# reed-door-sensor.net
KiCad netlist of a schematic drawn in EAGLE
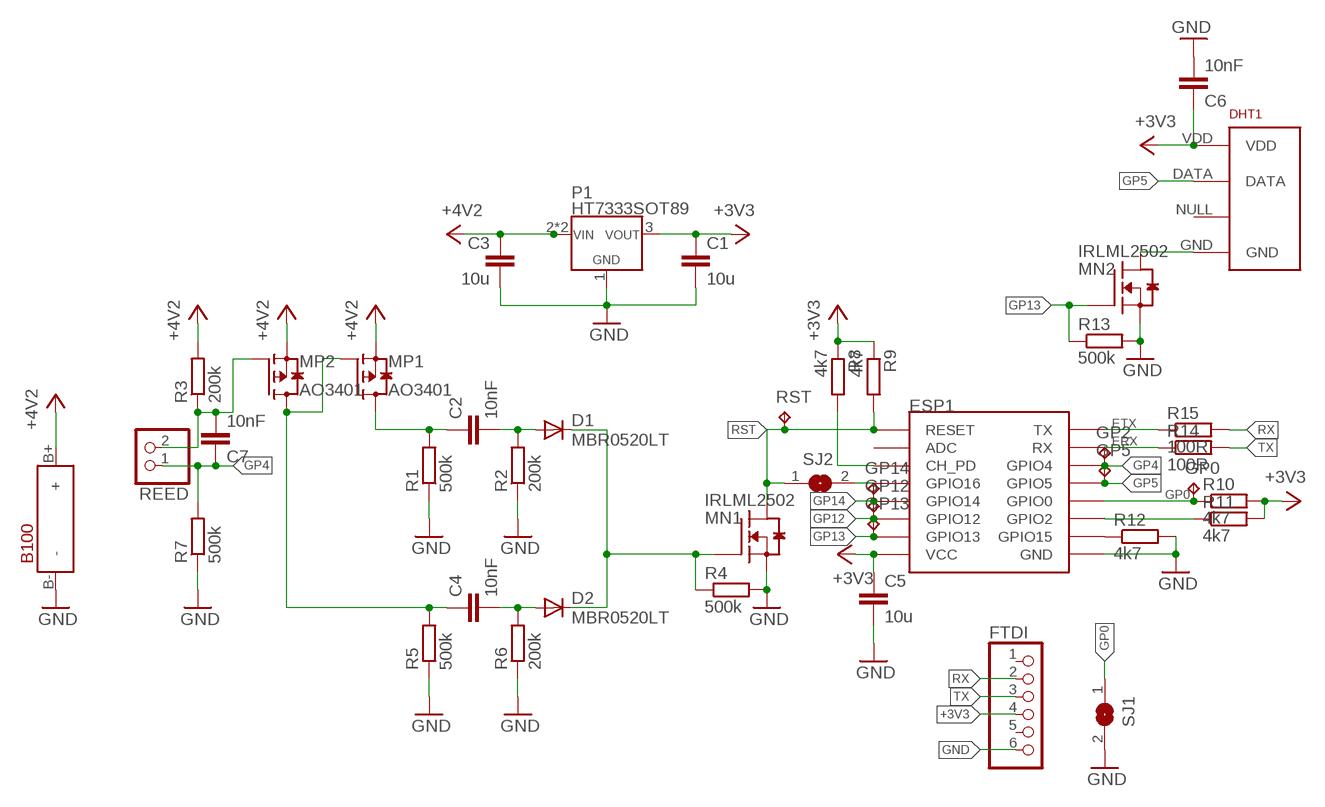
[diagram p0: schematic, sheet 1]

(export (version "E")
  (design (tool "Eeschema 10.0.6"))
  (components
    (comp (ref "B100")
      (value "18650_1X")
      (footprint "eagle-import:18650_HOLDER_1X")
      (libsource (lib "eagle-import") (part "18650_1X"))
    )
    (comp (ref "C1")
      (value "10u")
      (footprint "eagle-import:C1206")
      (libsource (lib "eagle-import") (part "C-EUC1206"))
    )
    (comp (ref "C2")
      (value "10nF")
      (footprint "eagle-import:C0805")
      (libsource (lib "eagle-import") (part "C-EUC0805"))
    )
    (comp (ref "C3")
      (value "10u")
      (footprint "eagle-import:C1206")
      (libsource (lib "eagle-import") (part "C-EUC1206"))
    )
    (comp (ref "C4")
      (value "10nF")
      (footprint "eagle-import:C0805")
      (libsource (lib "eagle-import") (part "C-EUC0805"))
    )
    (comp (ref "C5")
      (value "10u")
      (footprint "eagle-import:C1206")
      (libsource (lib "eagle-import") (part "C-EUC1206"))
    )
    (comp (ref "C6")
      (value "10nF")
      (footprint "eagle-import:C0805")
      (libsource (lib "eagle-import") (part "C-EUC0805"))
    )
    (comp (ref "C7")
      (value "10nF")
      (footprint "eagle-import:C0805")
      (libsource (lib "eagle-import") (part "C-EUC0805"))
    )
    (comp (ref "D1")
      (value "MBR0520LT")
      (footprint "eagle-import:SOD123")
      (libsource (lib "eagle-import") (part "MBR0520LT"))
    )
    (comp (ref "D2")
      (value "MBR0520LT")
      (footprint "eagle-import:SOD123")
      (libsource (lib "eagle-import") (part "MBR0520LT"))
    )
    (comp (ref "DHT1")
      (value "RHT03_DHT-22_AM2302")
      (footprint "eagle-import:RHT03_DHT-22")
      (libsource (lib "eagle-import") (part "RHT03_DHT-22_AM2302"))
    )
    (comp (ref "ESP1")
      (value "ESP12SMD")
      (footprint "eagle-import:ESP12-SMD")
      (libsource (lib "eagle-import") (part "ESP12SMD"))
    )
    (comp (ref "FTDI")
      (value "PINHD-1X06_2.54-S")
      (footprint "eagle-import:1X06-S")
      (libsource (lib "eagle-import") (part "PINHD-1X06_2.54-S"))
    )
    (comp (ref "GP0")
      (value "TPB2,54")
      (footprint "eagle-import:B2,54")
      (libsource (lib "eagle-import") (part "TPB2,54"))
    )
    (comp (ref "GP2")
      (value "TPB1,27")
      (footprint "eagle-import:B1,27")
      (libsource (lib "eagle-import") (part "TPB1,27"))
    )
    (comp (ref "GP5")
      (value "TPB1,27")
      (footprint "eagle-import:B1,27")
      (libsource (lib "eagle-import") (part "TPB1,27"))
    )
    (comp (ref "GP12")
      (value "TPB1,27")
      (footprint "eagle-import:B1,27")
      (libsource (lib "eagle-import") (part "TPB1,27"))
    )
    (comp (ref "GP13")
      (value "TPB1,27")
      (footprint "eagle-import:B1,27")
      (libsource (lib "eagle-import") (part "TPB1,27"))
    )
    (comp (ref "GP14")
      (value "TPB1,27")
      (footprint "eagle-import:B1,27")
      (libsource (lib "eagle-import") (part "TPB1,27"))
    )
    (comp (ref "MN1")
      (value "IRLML2502")
      (footprint "eagle-import:SOT23")
      (libsource (lib "eagle-import") (part "N-CH_IRLML2502"))
    )
    (comp (ref "MN2")
      (value "IRLML2502")
      (footprint "eagle-import:SOT23")
      (libsource (lib "eagle-import") (part "N-CH_IRLML2502"))
    )
    (comp (ref "MP1")
      (value "AO3401")
      (footprint "eagle-import:SOT23")
      (libsource (lib "eagle-import") (part "P-CH_AO3401"))
    )
    (comp (ref "MP2")
      (value "AO3401")
      (footprint "eagle-import:SOT23")
      (libsource (lib "eagle-import") (part "P-CH_AO3401"))
    )
    (comp (ref "P1")
      (value "HT7333SOT89")
      (footprint "eagle-import:SOT89")
      (libsource (lib "eagle-import") (part "HT7333SOT89"))
    )
    (comp (ref "R1")
      (value "500k")
      (footprint "eagle-import:M0805")
      (libsource (lib "eagle-import") (part "R-EU_M0805"))
    )
    (comp (ref "R2")
      (value "200k")
      (footprint "eagle-import:M0805")
      (libsource (lib "eagle-import") (part "R-EU_M0805"))
    )
    (comp (ref "R3")
      (value "200k")
      (footprint "eagle-import:M0805")
      (libsource (lib "eagle-import") (part "R-EU_M0805"))
    )
    (comp (ref "R4")
      (value "500k")
      (footprint "eagle-import:M0805")
      (libsource (lib "eagle-import") (part "R-EU_M0805"))
    )
    (comp (ref "R5")
      (value "500k")
      (footprint "eagle-import:M0805")
      (libsource (lib "eagle-import") (part "R-EU_M0805"))
    )
    (comp (ref "R6")
      (value "200k")
      (footprint "eagle-import:M0805")
      (libsource (lib "eagle-import") (part "R-EU_M0805"))
    )
    (comp (ref "R7")
      (value "500k")
      (footprint "eagle-import:M0805")
      (libsource (lib "eagle-import") (part "R-EU_M0805"))
    )
    (comp (ref "R8")
      (value "4k7")
      (footprint "eagle-import:M0805")
      (libsource (lib "eagle-import") (part "R-EU_M0805"))
    )
    (comp (ref "R9")
      (value "4k7")
      (footprint "eagle-import:M0805")
      (libsource (lib "eagle-import") (part "R-EU_M0805"))
    )
    (comp (ref "R10")
      (value "4k7")
      (footprint "eagle-import:M0805")
      (libsource (lib "eagle-import") (part "R-EU_M0805"))
    )
    (comp (ref "R11")
      (value "4k7")
      (footprint "eagle-import:M0805")
      (libsource (lib "eagle-import") (part "R-EU_M0805"))
    )
    (comp (ref "R12")
      (value "4k7")
      (footprint "eagle-import:M0805")
      (libsource (lib "eagle-import") (part "R-EU_M0805"))
    )
    (comp (ref "R13")
      (value "500k")
      (footprint "eagle-import:M0805")
      (libsource (lib "eagle-import") (part "R-EU_M0805"))
    )
    (comp (ref "R14")
      (value "100R")
      (footprint "eagle-import:M0805")
      (libsource (lib "eagle-import") (part "R-EU_M0805"))
    )
    (comp (ref "R15")
      (value "100R")
      (footprint "eagle-import:M0805")
      (libsource (lib "eagle-import") (part "R-EU_M0805"))
    )
    (comp (ref "REED")
      (value "PINHD-1X02_2.54")
      (footprint "eagle-import:1X02")
      (libsource (lib "eagle-import") (part "PINHD-1X02_2.54"))
    )
    (comp (ref "RST")
      (value "TPB2,54")
      (footprint "eagle-import:B2,54")
      (libsource (lib "eagle-import") (part "TPB2,54"))
    )
    (comp (ref "SJ1") (value "SJ") (footprint "eagle-import:SJ") (libsource (lib "eagle-import") (part "SJ")))
    (comp (ref "SJ2") (value "SJ") (footprint "eagle-import:SJ") (libsource (lib "eagle-import") (part "SJ")))
  )
  (nets
    (net (code "1") (name "+3V3") (class "Default")
      (node (ref "C1") (pin "1") (pinfunction "1_1") (pintype "passive"))
      (node (ref "C5") (pin "1") (pinfunction "1_1") (pintype "passive"))
      (node (ref "C6") (pin "1") (pinfunction "1_1") (pintype "passive"))
      (node (ref "DHT1") (pin "VDD") (pinfunction "VDD_VDD") (pintype "power_in"))
      (node (ref "ESP1") (pin "VCC") (pinfunction "VCC_VCC") (pintype "bidirectional"))
      (node (ref "FTDI") (pin "4") (pinfunction "4_4") (pintype "passive"))
      (node (ref "P1") (pin "3") (pinfunction "VOUT_3") (pintype "power_in"))
      (node (ref "R10") (pin "2") (pinfunction "2_2") (pintype "passive"))
      (node (ref "R11") (pin "2") (pinfunction "2_2") (pintype "passive"))
      (node (ref "R8") (pin "1") (pinfunction "1_1") (pintype "passive"))
      (node (ref "R9") (pin "1") (pinfunction "1_1") (pintype "passive"))
    )
    (net (code "2") (name "+4V2") (class "Default")
      (node (ref "B100") (pin "B+") (pinfunction "+_B+") (pintype "power_in"))
      (node (ref "C3") (pin "1") (pinfunction "1_1") (pintype "passive"))
      (node (ref "MP1") (pin "2") (pinfunction "S_2") (pintype "passive"))
      (node (ref "MP2") (pin "2") (pinfunction "S_2") (pintype "passive"))
      (node (ref "P1") (pin "2") (pinfunction "VIN_2") (pintype "power_in"))
      (node (ref "P1") (pin "2@1") (pinfunction "VIN_2@1") (pintype "power_in"))
      (node (ref "R3") (pin "2") (pinfunction "2_2") (pintype "passive"))
    )
    (net (code "3") (name "/ERX") (class "Default")
      (node (ref "ESP1") (pin "RXD0") (pinfunction "RX_RXD0") (pintype "bidirectional"))
      (node (ref "R14") (pin "1") (pinfunction "1_1") (pintype "passive"))
    )
    (net (code "4") (name "/ETX") (class "Default")
      (node (ref "ESP1") (pin "TXD0") (pinfunction "TX_TXD0") (pintype "bidirectional"))
      (node (ref "R15") (pin "1") (pinfunction "1_1") (pintype "passive"))
    )
    (net (code "5") (name "GND") (class "Default")
      (node (ref "B100") (pin "B-") (pinfunction "-_B-") (pintype "power_in"))
      (node (ref "C1") (pin "2") (pinfunction "2_2") (pintype "passive"))
      (node (ref "C3") (pin "2") (pinfunction "2_2") (pintype "passive"))
      (node (ref "C5") (pin "2") (pinfunction "2_2") (pintype "passive"))
      (node (ref "C6") (pin "2") (pinfunction "2_2") (pintype "passive"))
      (node (ref "ESP1") (pin "GND") (pinfunction "GND_GND") (pintype "bidirectional"))
      (node (ref "FTDI") (pin "6") (pinfunction "6_6") (pintype "passive"))
      (node (ref "MN1") (pin "2") (pinfunction "S_2") (pintype "passive"))
      (node (ref "MN2") (pin "2") (pinfunction "S_2") (pintype "passive"))
      (node (ref "P1") (pin "1") (pinfunction "GND_1") (pintype "power_in"))
      (node (ref "R1") (pin "1") (pinfunction "1_1") (pintype "passive"))
      (node (ref "R12") (pin "2") (pinfunction "2_2") (pintype "passive"))
      (node (ref "R13") (pin "2") (pinfunction "2_2") (pintype "passive"))
      (node (ref "R2") (pin "1") (pinfunction "1_1") (pintype "passive"))
      (node (ref "R4") (pin "2") (pinfunction "2_2") (pintype "passive"))
      (node (ref "R5") (pin "1") (pinfunction "1_1") (pintype "passive"))
      (node (ref "R6") (pin "1") (pinfunction "1_1") (pintype "passive"))
      (node (ref "R7") (pin "1") (pinfunction "1_1") (pintype "passive"))
      (node (ref "SJ1") (pin "2") (pinfunction "2_2") (pintype "passive"))
    )
    (net (code "6") (name "GP0") (class "Default")
      (node (ref "ESP1") (pin "GPIO0") (pinfunction "GPIO0_GPIO0") (pintype "bidirectional"))
      (node (ref "GP0") (pin "TP") (pinfunction "TP_TP") (pintype "input"))
      (node (ref "R10") (pin "1") (pinfunction "1_1") (pintype "passive"))
      (node (ref "SJ1") (pin "1") (pinfunction "1_1") (pintype "passive"))
    )
    (net (code "7") (name "GP4") (class "Default")
      (node (ref "C7") (pin "1") (pinfunction "1_1") (pintype "passive"))
      (node (ref "ESP1") (pin "GPIO4") (pinfunction "GPIO4_GPIO4") (pintype "bidirectional"))
      (node (ref "GP2") (pin "TP") (pinfunction "TP_TP") (pintype "input"))
      (node (ref "R7") (pin "2") (pinfunction "2_2") (pintype "passive"))
      (node (ref "REED") (pin "1") (pinfunction "1_1") (pintype "passive"))
    )
    (net (code "8") (name "GP5") (class "Default")
      (node (ref "DHT1") (pin "DATA") (pinfunction "DATA_DATA") (pintype "bidirectional"))
      (node (ref "ESP1") (pin "GPIO5") (pinfunction "GPIO5_GPIO5") (pintype "bidirectional"))
      (node (ref "GP5") (pin "TP") (pinfunction "TP_TP") (pintype "input"))
    )
    (net (code "9") (name "GP12") (class "Default")
      (node (ref "ESP1") (pin "GPIO12") (pinfunction "GPIO12_GPIO12") (pintype "bidirectional"))
      (node (ref "GP12") (pin "TP") (pinfunction "TP_TP") (pintype "input"))
    )
    (net (code "10") (name "GP13") (class "Default")
      (node (ref "ESP1") (pin "GPIO13") (pinfunction "GPIO13_GPIO13") (pintype "bidirectional"))
      (node (ref "GP13") (pin "TP") (pinfunction "TP_TP") (pintype "input"))
      (node (ref "MN2") (pin "1") (pinfunction "G_1") (pintype "passive"))
      (node (ref "R13") (pin "1") (pinfunction "1_1") (pintype "passive"))
    )
    (net (code "11") (name "GP14") (class "Default")
      (node (ref "ESP1") (pin "GPIO14") (pinfunction "GPIO14_GPIO14") (pintype "bidirectional"))
      (node (ref "GP14") (pin "TP") (pinfunction "TP_TP") (pintype "input"))
    )
    (net (code "12") (name "Net-(C2-Pad2)") (class "Default")
      (node (ref "C2") (pin "2") (pinfunction "2_2") (pintype "passive"))
      (node (ref "D1") (pin "A") (pinfunction "A_A") (pintype "passive"))
      (node (ref "R2") (pin "2") (pinfunction "2_2") (pintype "passive"))
    )
    (net (code "13") (name "Net-(C4-Pad2)") (class "Default")
      (node (ref "C4") (pin "2") (pinfunction "2_2") (pintype "passive"))
      (node (ref "D2") (pin "A") (pinfunction "A_A") (pintype "passive"))
      (node (ref "R6") (pin "2") (pinfunction "2_2") (pintype "passive"))
    )
    (net (code "14") (name "Net-(ESP1-PadCH_PD)") (class "Default")
      (node (ref "ESP1") (pin "CH_PD") (pinfunction "CH_PD_CH_PD") (pintype "bidirectional"))
      (node (ref "R8") (pin "2") (pinfunction "2_2") (pintype "passive"))
    )
    (net (code "15") (name "Net-(ESP1-PadGPIO2)") (class "Default")
      (node (ref "ESP1") (pin "GPIO2") (pinfunction "GPIO2_GPIO2") (pintype "bidirectional"))
      (node (ref "R11") (pin "1") (pinfunction "1_1") (pintype "passive"))
    )
    (net (code "16") (name "Net-(ESP1-PadGPIO15)") (class "Default")
      (node (ref "ESP1") (pin "GPIO15") (pinfunction "GPIO15_GPIO15") (pintype "bidirectional"))
      (node (ref "R12") (pin "1") (pinfunction "1_1") (pintype "passive"))
    )
    (net (code "17") (name "Net-(ESP1-PadGPIO16)") (class "Default")
      (node (ref "ESP1") (pin "GPIO16") (pinfunction "GPIO16_GPIO16") (pintype "bidirectional"))
      (node (ref "SJ2") (pin "2") (pinfunction "2_2") (pintype "passive"))
    )
    (net (code "18") (name "Net-(MN1-G)") (class "Default")
      (node (ref "D1") (pin "C") (pinfunction "C_C") (pintype "passive"))
      (node (ref "D2") (pin "C") (pinfunction "C_C") (pintype "passive"))
      (node (ref "MN1") (pin "1") (pinfunction "G_1") (pintype "passive"))
      (node (ref "R4") (pin "1") (pinfunction "1_1") (pintype "passive"))
    )
    (net (code "19") (name "Net-(MN2-D)") (class "Default")
      (node (ref "DHT1") (pin "GND") (pinfunction "GND_GND") (pintype "power_in"))
      (node (ref "MN2") (pin "3") (pinfunction "D_3") (pintype "passive"))
    )
    (net (code "20") (name "Net-(MP1-D)") (class "Default")
      (node (ref "C2") (pin "1") (pinfunction "1_1") (pintype "passive"))
      (node (ref "MP1") (pin "3") (pinfunction "D_3") (pintype "passive"))
      (node (ref "R1") (pin "2") (pinfunction "2_2") (pintype "passive"))
    )
    (net (code "21") (name "Net-(MP1-G)") (class "Default")
      (node (ref "C4") (pin "1") (pinfunction "1_1") (pintype "passive"))
      (node (ref "MP1") (pin "1") (pinfunction "G_1") (pintype "passive"))
      (node (ref "MP2") (pin "3") (pinfunction "D_3") (pintype "passive"))
      (node (ref "R5") (pin "2") (pinfunction "2_2") (pintype "passive"))
    )
    (net (code "22") (name "Net-(MP2-G)") (class "Default")
      (node (ref "C7") (pin "2") (pinfunction "2_2") (pintype "passive"))
      (node (ref "MP2") (pin "1") (pinfunction "G_1") (pintype "passive"))
      (node (ref "R3") (pin "1") (pinfunction "1_1") (pintype "passive"))
      (node (ref "REED") (pin "2") (pinfunction "2_2") (pintype "passive"))
    )
    (net (code "23") (name "RST") (class "Default")
      (node (ref "ESP1") (pin "RESET") (pinfunction "RESET_RESET") (pintype "bidirectional"))
      (node (ref "MN1") (pin "3") (pinfunction "D_3") (pintype "passive"))
      (node (ref "R9") (pin "2") (pinfunction "2_2") (pintype "passive"))
      (node (ref "RST") (pin "TP") (pinfunction "TP_TP") (pintype "input"))
      (node (ref "SJ2") (pin "1") (pinfunction "1_1") (pintype "passive"))
    )
    (net (code "24") (name "RX") (class "Default")
      (node (ref "FTDI") (pin "2") (pinfunction "2_2") (pintype "passive"))
      (node (ref "R15") (pin "2") (pinfunction "2_2") (pintype "passive"))
    )
    (net (code "25") (name "TX") (class "Default")
      (node (ref "FTDI") (pin "3") (pinfunction "3_3") (pintype "passive"))
      (node (ref "R14") (pin "2") (pinfunction "2_2") (pintype "passive"))
    )
    (net (code "26") (name "unconnected-(DHT1-PadNULL)") (class "Default")
      (node (ref "DHT1") (pin "NULL") (pinfunction "NULL_NULL") (pintype "no_connect"))
    )
    (net (code "27") (name "unconnected-(ESP1-PadADC)") (class "Default")
      (node (ref "ESP1") (pin "ADC") (pinfunction "ADC_ADC") (pintype "bidirectional"))
    )
    (net (code "28") (name "unconnected-(FTDI-Pad1)") (class "Default")
      (node (ref "FTDI") (pin "1") (pinfunction "1_1") (pintype "passive"))
    )
    (net (code "29") (name "unconnected-(FTDI-Pad5)") (class "Default")
      (node (ref "FTDI") (pin "5") (pinfunction "5_5") (pintype "passive"))
    )
  )
)
